# Terrariumsteuerung.net
KiCad netlist of a schematic drawn in EAGLE
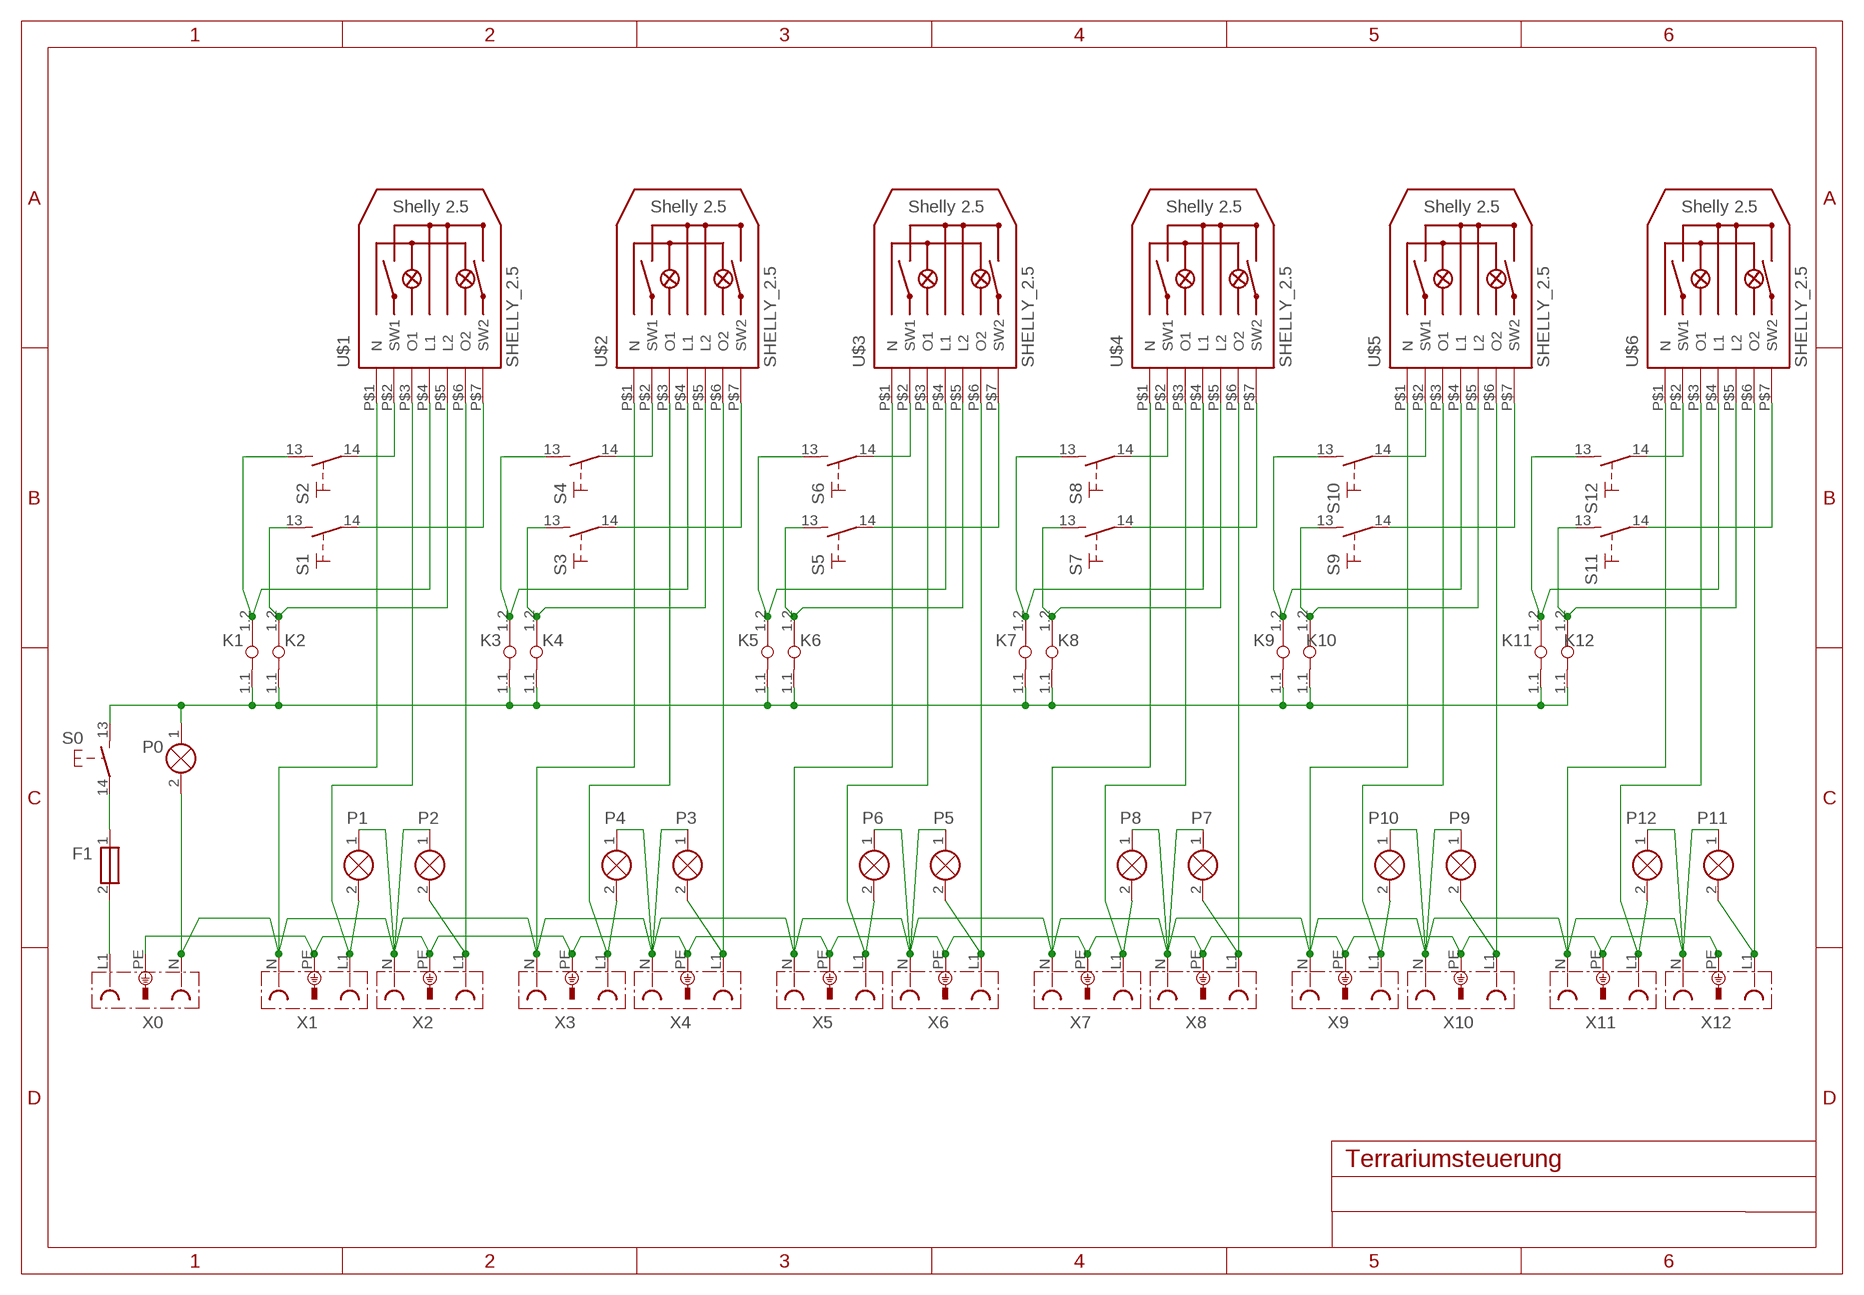
[diagram p0: schematic, sheet 1]

(export (version "E")
  (design (tool "Eeschema 10.0.6"))
  (components
    (comp (ref "F1")
      (value "SICHERUNG_1-POL")
      (footprint "eagle-import:SICHERUNG_1-POL")
      (libsource (lib "eagle-import") (part "SICHERUNG_1-POL"))
    )
    (comp (ref "K1")
      (value "KLEMME_1-1")
      (footprint "eagle-import:KLEMME_1-1")
      (libsource (lib "eagle-import") (part "KLEMME_1-1"))
    )
    (comp (ref "K2")
      (value "KLEMME_1-1")
      (footprint "eagle-import:KLEMME_1-1")
      (libsource (lib "eagle-import") (part "KLEMME_1-1"))
    )
    (comp (ref "K3")
      (value "KLEMME_1-1")
      (footprint "eagle-import:KLEMME_1-1")
      (libsource (lib "eagle-import") (part "KLEMME_1-1"))
    )
    (comp (ref "K4")
      (value "KLEMME_1-1")
      (footprint "eagle-import:KLEMME_1-1")
      (libsource (lib "eagle-import") (part "KLEMME_1-1"))
    )
    (comp (ref "K5")
      (value "KLEMME_1-1")
      (footprint "eagle-import:KLEMME_1-1")
      (libsource (lib "eagle-import") (part "KLEMME_1-1"))
    )
    (comp (ref "K6")
      (value "KLEMME_1-1")
      (footprint "eagle-import:KLEMME_1-1")
      (libsource (lib "eagle-import") (part "KLEMME_1-1"))
    )
    (comp (ref "K7")
      (value "KLEMME_1-1")
      (footprint "eagle-import:KLEMME_1-1")
      (libsource (lib "eagle-import") (part "KLEMME_1-1"))
    )
    (comp (ref "K8")
      (value "KLEMME_1-1")
      (footprint "eagle-import:KLEMME_1-1")
      (libsource (lib "eagle-import") (part "KLEMME_1-1"))
    )
    (comp (ref "K9")
      (value "KLEMME_1-1")
      (footprint "eagle-import:KLEMME_1-1")
      (libsource (lib "eagle-import") (part "KLEMME_1-1"))
    )
    (comp (ref "K10")
      (value "KLEMME_1-1")
      (footprint "eagle-import:KLEMME_1-1")
      (libsource (lib "eagle-import") (part "KLEMME_1-1"))
    )
    (comp (ref "K11")
      (value "KLEMME_1-1")
      (footprint "eagle-import:KLEMME_1-1")
      (libsource (lib "eagle-import") (part "KLEMME_1-1"))
    )
    (comp (ref "K12")
      (value "KLEMME_1-1")
      (footprint "eagle-import:KLEMME_1-1")
      (libsource (lib "eagle-import") (part "KLEMME_1-1"))
    )
    (comp (ref "P0")
      (value "SIGNALLAMPE")
      (footprint "eagle-import:LAMPE")
      (libsource (lib "eagle-import") (part "SIGNALLAMPE"))
    )
    (comp (ref "P1")
      (value "SIGNALLAMPE")
      (footprint "eagle-import:LAMPE")
      (libsource (lib "eagle-import") (part "SIGNALLAMPE"))
    )
    (comp (ref "P2")
      (value "SIGNALLAMPE")
      (footprint "eagle-import:LAMPE")
      (libsource (lib "eagle-import") (part "SIGNALLAMPE"))
    )
    (comp (ref "P3")
      (value "SIGNALLAMPE")
      (footprint "eagle-import:LAMPE")
      (libsource (lib "eagle-import") (part "SIGNALLAMPE"))
    )
    (comp (ref "P4")
      (value "SIGNALLAMPE")
      (footprint "eagle-import:LAMPE")
      (libsource (lib "eagle-import") (part "SIGNALLAMPE"))
    )
    (comp (ref "P5")
      (value "SIGNALLAMPE")
      (footprint "eagle-import:LAMPE")
      (libsource (lib "eagle-import") (part "SIGNALLAMPE"))
    )
    (comp (ref "P6")
      (value "SIGNALLAMPE")
      (footprint "eagle-import:LAMPE")
      (libsource (lib "eagle-import") (part "SIGNALLAMPE"))
    )
    (comp (ref "P7")
      (value "SIGNALLAMPE")
      (footprint "eagle-import:LAMPE")
      (libsource (lib "eagle-import") (part "SIGNALLAMPE"))
    )
    (comp (ref "P8")
      (value "SIGNALLAMPE")
      (footprint "eagle-import:LAMPE")
      (libsource (lib "eagle-import") (part "SIGNALLAMPE"))
    )
    (comp (ref "P9")
      (value "SIGNALLAMPE")
      (footprint "eagle-import:LAMPE")
      (libsource (lib "eagle-import") (part "SIGNALLAMPE"))
    )
    (comp (ref "P10")
      (value "SIGNALLAMPE")
      (footprint "eagle-import:LAMPE")
      (libsource (lib "eagle-import") (part "SIGNALLAMPE"))
    )
    (comp (ref "P11")
      (value "SIGNALLAMPE")
      (footprint "eagle-import:LAMPE")
      (libsource (lib "eagle-import") (part "SIGNALLAMPE"))
    )
    (comp (ref "P12")
      (value "SIGNALLAMPE")
      (footprint "eagle-import:LAMPE")
      (libsource (lib "eagle-import") (part "SIGNALLAMPE"))
    )
    (comp (ref "S0")
      (value "TASTER_SCHLIESSER")
      (footprint "eagle-import:EINTASTER")
      (libsource (lib "eagle-import") (part "TASTER_SCHLIESSER"))
    )
    (comp (ref "S1")
      (value "SCHLIESSER_KIPPSCHALTER")
      (footprint "eagle-import:SCHLIESSER_KIPPSCHALTER")
      (libsource (lib "eagle-import") (part "SCHLIESSER_KIPPSCHALTER"))
    )
    (comp (ref "S2")
      (value "SCHLIESSER_KIPPSCHALTER")
      (footprint "eagle-import:SCHLIESSER_KIPPSCHALTER")
      (libsource (lib "eagle-import") (part "SCHLIESSER_KIPPSCHALTER"))
    )
    (comp (ref "S3")
      (value "SCHLIESSER_KIPPSCHALTER")
      (footprint "eagle-import:SCHLIESSER_KIPPSCHALTER")
      (libsource (lib "eagle-import") (part "SCHLIESSER_KIPPSCHALTER"))
    )
    (comp (ref "S4")
      (value "SCHLIESSER_KIPPSCHALTER")
      (footprint "eagle-import:SCHLIESSER_KIPPSCHALTER")
      (libsource (lib "eagle-import") (part "SCHLIESSER_KIPPSCHALTER"))
    )
    (comp (ref "S5")
      (value "SCHLIESSER_KIPPSCHALTER")
      (footprint "eagle-import:SCHLIESSER_KIPPSCHALTER")
      (libsource (lib "eagle-import") (part "SCHLIESSER_KIPPSCHALTER"))
    )
    (comp (ref "S6")
      (value "SCHLIESSER_KIPPSCHALTER")
      (footprint "eagle-import:SCHLIESSER_KIPPSCHALTER")
      (libsource (lib "eagle-import") (part "SCHLIESSER_KIPPSCHALTER"))
    )
    (comp (ref "S7")
      (value "SCHLIESSER_KIPPSCHALTER")
      (footprint "eagle-import:SCHLIESSER_KIPPSCHALTER")
      (libsource (lib "eagle-import") (part "SCHLIESSER_KIPPSCHALTER"))
    )
    (comp (ref "S8")
      (value "SCHLIESSER_KIPPSCHALTER")
      (footprint "eagle-import:SCHLIESSER_KIPPSCHALTER")
      (libsource (lib "eagle-import") (part "SCHLIESSER_KIPPSCHALTER"))
    )
    (comp (ref "S9")
      (value "SCHLIESSER_KIPPSCHALTER")
      (footprint "eagle-import:SCHLIESSER_KIPPSCHALTER")
      (libsource (lib "eagle-import") (part "SCHLIESSER_KIPPSCHALTER"))
    )
    (comp (ref "S10")
      (value "SCHLIESSER_KIPPSCHALTER")
      (footprint "eagle-import:SCHLIESSER_KIPPSCHALTER")
      (libsource (lib "eagle-import") (part "SCHLIESSER_KIPPSCHALTER"))
    )
    (comp (ref "S11")
      (value "SCHLIESSER_KIPPSCHALTER")
      (footprint "eagle-import:SCHLIESSER_KIPPSCHALTER")
      (libsource (lib "eagle-import") (part "SCHLIESSER_KIPPSCHALTER"))
    )
    (comp (ref "S12")
      (value "SCHLIESSER_KIPPSCHALTER")
      (footprint "eagle-import:SCHLIESSER_KIPPSCHALTER")
      (libsource (lib "eagle-import") (part "SCHLIESSER_KIPPSCHALTER"))
    )
    (comp (ref "U$1")
      (value "SHELLY_2.5")
      (footprint "eagle-import:SHELLY_2.5")
      (libsource (lib "eagle-import") (part "SHELLY_2.5"))
    )
    (comp (ref "U$2")
      (value "SHELLY_2.5")
      (footprint "eagle-import:SHELLY_2.5")
      (libsource (lib "eagle-import") (part "SHELLY_2.5"))
    )
    (comp (ref "U$3")
      (value "SHELLY_2.5")
      (footprint "eagle-import:SHELLY_2.5")
      (libsource (lib "eagle-import") (part "SHELLY_2.5"))
    )
    (comp (ref "U$4")
      (value "SHELLY_2.5")
      (footprint "eagle-import:SHELLY_2.5")
      (libsource (lib "eagle-import") (part "SHELLY_2.5"))
    )
    (comp (ref "U$5")
      (value "SHELLY_2.5")
      (footprint "eagle-import:SHELLY_2.5")
      (libsource (lib "eagle-import") (part "SHELLY_2.5"))
    )
    (comp (ref "U$6")
      (value "SHELLY_2.5")
      (footprint "eagle-import:SHELLY_2.5")
      (libsource (lib "eagle-import") (part "SHELLY_2.5"))
    )
    (comp (ref "X0")
      (value "STECKDOSE")
      (footprint "eagle-import:STECKDOSE")
      (libsource (lib "eagle-import") (part "STECKDOSE"))
    )
    (comp (ref "X1")
      (value "STECKDOSE")
      (footprint "eagle-import:STECKDOSE")
      (libsource (lib "eagle-import") (part "STECKDOSE"))
    )
    (comp (ref "X2")
      (value "STECKDOSE")
      (footprint "eagle-import:STECKDOSE")
      (libsource (lib "eagle-import") (part "STECKDOSE"))
    )
    (comp (ref "X3")
      (value "STECKDOSE")
      (footprint "eagle-import:STECKDOSE")
      (libsource (lib "eagle-import") (part "STECKDOSE"))
    )
    (comp (ref "X4")
      (value "STECKDOSE")
      (footprint "eagle-import:STECKDOSE")
      (libsource (lib "eagle-import") (part "STECKDOSE"))
    )
    (comp (ref "X5")
      (value "STECKDOSE")
      (footprint "eagle-import:STECKDOSE")
      (libsource (lib "eagle-import") (part "STECKDOSE"))
    )
    (comp (ref "X6")
      (value "STECKDOSE")
      (footprint "eagle-import:STECKDOSE")
      (libsource (lib "eagle-import") (part "STECKDOSE"))
    )
    (comp (ref "X7")
      (value "STECKDOSE")
      (footprint "eagle-import:STECKDOSE")
      (libsource (lib "eagle-import") (part "STECKDOSE"))
    )
    (comp (ref "X8")
      (value "STECKDOSE")
      (footprint "eagle-import:STECKDOSE")
      (libsource (lib "eagle-import") (part "STECKDOSE"))
    )
    (comp (ref "X9")
      (value "STECKDOSE")
      (footprint "eagle-import:STECKDOSE")
      (libsource (lib "eagle-import") (part "STECKDOSE"))
    )
    (comp (ref "X10")
      (value "STECKDOSE")
      (footprint "eagle-import:STECKDOSE")
      (libsource (lib "eagle-import") (part "STECKDOSE"))
    )
    (comp (ref "X11")
      (value "STECKDOSE")
      (footprint "eagle-import:STECKDOSE")
      (libsource (lib "eagle-import") (part "STECKDOSE"))
    )
    (comp (ref "X12")
      (value "STECKDOSE")
      (footprint "eagle-import:STECKDOSE")
      (libsource (lib "eagle-import") (part "STECKDOSE"))
    )
  )
  (nets
    (net (code "1") (name "Net-(F1-Pad1)") (class "Default")
      (node (ref "F1") (pin "1") (pinfunction "1_1") (pintype "passive"))
      (node (ref "S0") (pin "14") (pinfunction "14_14") (pintype "passive"))
    )
    (net (code "2") (name "Net-(F1-Pad2)") (class "Default")
      (node (ref "F1") (pin "2") (pinfunction "2_2") (pintype "passive"))
      (node (ref "X0") (pin "L1") (pinfunction "L1_L1") (pintype "passive"))
    )
    (net (code "3") (name "Net-(P0-X1)") (class "Default")
      (node (ref "K1") (pin "1.1") (pinfunction "1.1_1.1") (pintype "passive"))
      (node (ref "K10") (pin "1.1") (pinfunction "1.1_1.1") (pintype "passive"))
      (node (ref "K11") (pin "1.1") (pinfunction "1.1_1.1") (pintype "passive"))
      (node (ref "K12") (pin "1.1") (pinfunction "1.1_1.1") (pintype "passive"))
      (node (ref "K2") (pin "1.1") (pinfunction "1.1_1.1") (pintype "passive"))
      (node (ref "K3") (pin "1.1") (pinfunction "1.1_1.1") (pintype "passive"))
      (node (ref "K4") (pin "1.1") (pinfunction "1.1_1.1") (pintype "passive"))
      (node (ref "K5") (pin "1.1") (pinfunction "1.1_1.1") (pintype "passive"))
      (node (ref "K6") (pin "1.1") (pinfunction "1.1_1.1") (pintype "passive"))
      (node (ref "K7") (pin "1.1") (pinfunction "1.1_1.1") (pintype "passive"))
      (node (ref "K8") (pin "1.1") (pinfunction "1.1_1.1") (pintype "passive"))
      (node (ref "K9") (pin "1.1") (pinfunction "1.1_1.1") (pintype "passive"))
      (node (ref "P0") (pin "1") (pinfunction "X1_1") (pintype "passive"))
      (node (ref "S0") (pin "13") (pinfunction "13_13") (pintype "passive"))
    )
    (net (code "4") (name "Net-(P0-X2)") (class "Default")
      (node (ref "P0") (pin "2") (pinfunction "X2_2") (pintype "passive"))
      (node (ref "P1") (pin "1") (pinfunction "X1_1") (pintype "passive"))
      (node (ref "P10") (pin "1") (pinfunction "X1_1") (pintype "passive"))
      (node (ref "P11") (pin "1") (pinfunction "X1_1") (pintype "passive"))
      (node (ref "P12") (pin "1") (pinfunction "X1_1") (pintype "passive"))
      (node (ref "P2") (pin "1") (pinfunction "X1_1") (pintype "passive"))
      (node (ref "P3") (pin "1") (pinfunction "X1_1") (pintype "passive"))
      (node (ref "P4") (pin "1") (pinfunction "X1_1") (pintype "passive"))
      (node (ref "P5") (pin "1") (pinfunction "X1_1") (pintype "passive"))
      (node (ref "P6") (pin "1") (pinfunction "X1_1") (pintype "passive"))
      (node (ref "P7") (pin "1") (pinfunction "X1_1") (pintype "passive"))
      (node (ref "P8") (pin "1") (pinfunction "X1_1") (pintype "passive"))
      (node (ref "P9") (pin "1") (pinfunction "X1_1") (pintype "passive"))
      (node (ref "U$1") (pin "P$1") (pinfunction "N_P$1") (pintype "bidirectional"))
      (node (ref "U$2") (pin "P$1") (pinfunction "N_P$1") (pintype "bidirectional"))
      (node (ref "U$3") (pin "P$1") (pinfunction "N_P$1") (pintype "bidirectional"))
      (node (ref "U$4") (pin "P$1") (pinfunction "N_P$1") (pintype "bidirectional"))
      (node (ref "U$5") (pin "P$1") (pinfunction "N_P$1") (pintype "bidirectional"))
      (node (ref "U$6") (pin "P$1") (pinfunction "N_P$1") (pintype "bidirectional"))
      (node (ref "X0") (pin "N") (pinfunction "N_N") (pintype "passive"))
      (node (ref "X1") (pin "N") (pinfunction "N_N") (pintype "passive"))
      (node (ref "X10") (pin "N") (pinfunction "N_N") (pintype "passive"))
      (node (ref "X11") (pin "N") (pinfunction "N_N") (pintype "passive"))
      (node (ref "X12") (pin "N") (pinfunction "N_N") (pintype "passive"))
      (node (ref "X2") (pin "N") (pinfunction "N_N") (pintype "passive"))
      (node (ref "X3") (pin "N") (pinfunction "N_N") (pintype "passive"))
      (node (ref "X4") (pin "N") (pinfunction "N_N") (pintype "passive"))
      (node (ref "X5") (pin "N") (pinfunction "N_N") (pintype "passive"))
      (node (ref "X6") (pin "N") (pinfunction "N_N") (pintype "passive"))
      (node (ref "X7") (pin "N") (pinfunction "N_N") (pintype "passive"))
      (node (ref "X8") (pin "N") (pinfunction "N_N") (pintype "passive"))
      (node (ref "X9") (pin "N") (pinfunction "N_N") (pintype "passive"))
    )
    (net (code "5") (name "Net-(P1-X2)") (class "Default")
      (node (ref "P1") (pin "2") (pinfunction "X2_2") (pintype "passive"))
      (node (ref "U$1") (pin "P$3") (pinfunction "O1_P$3") (pintype "bidirectional"))
      (node (ref "X1") (pin "L1") (pinfunction "L1_L1") (pintype "passive"))
    )
    (net (code "6") (name "Net-(P2-X2)") (class "Default")
      (node (ref "P2") (pin "2") (pinfunction "X2_2") (pintype "passive"))
      (node (ref "U$1") (pin "P$6") (pinfunction "O2_P$6") (pintype "bidirectional"))
      (node (ref "X2") (pin "L1") (pinfunction "L1_L1") (pintype "passive"))
    )
    (net (code "7") (name "Net-(P3-X2)") (class "Default")
      (node (ref "P3") (pin "2") (pinfunction "X2_2") (pintype "passive"))
      (node (ref "U$2") (pin "P$6") (pinfunction "O2_P$6") (pintype "bidirectional"))
      (node (ref "X4") (pin "L1") (pinfunction "L1_L1") (pintype "passive"))
    )
    (net (code "8") (name "Net-(P4-X2)") (class "Default")
      (node (ref "P4") (pin "2") (pinfunction "X2_2") (pintype "passive"))
      (node (ref "U$2") (pin "P$3") (pinfunction "O1_P$3") (pintype "bidirectional"))
      (node (ref "X3") (pin "L1") (pinfunction "L1_L1") (pintype "passive"))
    )
    (net (code "9") (name "Net-(P5-X2)") (class "Default")
      (node (ref "P5") (pin "2") (pinfunction "X2_2") (pintype "passive"))
      (node (ref "U$3") (pin "P$6") (pinfunction "O2_P$6") (pintype "bidirectional"))
      (node (ref "X6") (pin "L1") (pinfunction "L1_L1") (pintype "passive"))
    )
    (net (code "10") (name "Net-(P6-X2)") (class "Default")
      (node (ref "P6") (pin "2") (pinfunction "X2_2") (pintype "passive"))
      (node (ref "U$3") (pin "P$3") (pinfunction "O1_P$3") (pintype "bidirectional"))
      (node (ref "X5") (pin "L1") (pinfunction "L1_L1") (pintype "passive"))
    )
    (net (code "11") (name "Net-(P7-X2)") (class "Default")
      (node (ref "P7") (pin "2") (pinfunction "X2_2") (pintype "passive"))
      (node (ref "U$4") (pin "P$6") (pinfunction "O2_P$6") (pintype "bidirectional"))
      (node (ref "X8") (pin "L1") (pinfunction "L1_L1") (pintype "passive"))
    )
    (net (code "12") (name "Net-(P8-X2)") (class "Default")
      (node (ref "P8") (pin "2") (pinfunction "X2_2") (pintype "passive"))
      (node (ref "U$4") (pin "P$3") (pinfunction "O1_P$3") (pintype "bidirectional"))
      (node (ref "X7") (pin "L1") (pinfunction "L1_L1") (pintype "passive"))
    )
    (net (code "13") (name "Net-(P9-X2)") (class "Default")
      (node (ref "P9") (pin "2") (pinfunction "X2_2") (pintype "passive"))
      (node (ref "U$5") (pin "P$6") (pinfunction "O2_P$6") (pintype "bidirectional"))
      (node (ref "X10") (pin "L1") (pinfunction "L1_L1") (pintype "passive"))
    )
    (net (code "14") (name "Net-(P10-X2)") (class "Default")
      (node (ref "P10") (pin "2") (pinfunction "X2_2") (pintype "passive"))
      (node (ref "U$5") (pin "P$3") (pinfunction "O1_P$3") (pintype "bidirectional"))
      (node (ref "X9") (pin "L1") (pinfunction "L1_L1") (pintype "passive"))
    )
    (net (code "15") (name "Net-(P11-X2)") (class "Default")
      (node (ref "P11") (pin "2") (pinfunction "X2_2") (pintype "passive"))
      (node (ref "U$6") (pin "P$6") (pinfunction "O2_P$6") (pintype "bidirectional"))
      (node (ref "X12") (pin "L1") (pinfunction "L1_L1") (pintype "passive"))
    )
    (net (code "16") (name "Net-(P12-X2)") (class "Default")
      (node (ref "P12") (pin "2") (pinfunction "X2_2") (pintype "passive"))
      (node (ref "U$6") (pin "P$3") (pinfunction "O1_P$3") (pintype "bidirectional"))
      (node (ref "X11") (pin "L1") (pinfunction "L1_L1") (pintype "passive"))
    )
    (net (code "17") (name "Net-(S1-3)") (class "Default")
      (node (ref "K2") (pin "1.2") (pinfunction "1.2_1.2") (pintype "passive"))
      (node (ref "S1") (pin "13") (pinfunction "3_13") (pintype "input"))
      (node (ref "U$1") (pin "P$5") (pinfunction "L2_P$5") (pintype "bidirectional"))
    )
    (net (code "18") (name "Net-(S1-4)") (class "Default")
      (node (ref "S1") (pin "14") (pinfunction "4_14") (pintype "input"))
      (node (ref "U$1") (pin "P$7") (pinfunction "SW2_P$7") (pintype "bidirectional"))
    )
    (net (code "19") (name "Net-(S2-3)") (class "Default")
      (node (ref "K1") (pin "1.2") (pinfunction "1.2_1.2") (pintype "passive"))
      (node (ref "S2") (pin "13") (pinfunction "3_13") (pintype "input"))
      (node (ref "U$1") (pin "P$4") (pinfunction "L1_P$4") (pintype "bidirectional"))
    )
    (net (code "20") (name "Net-(S2-4)") (class "Default")
      (node (ref "S2") (pin "14") (pinfunction "4_14") (pintype "input"))
      (node (ref "U$1") (pin "P$2") (pinfunction "SW1_P$2") (pintype "bidirectional"))
    )
    (net (code "21") (name "Net-(S3-3)") (class "Default")
      (node (ref "K4") (pin "1.2") (pinfunction "1.2_1.2") (pintype "passive"))
      (node (ref "S3") (pin "13") (pinfunction "3_13") (pintype "input"))
      (node (ref "U$2") (pin "P$5") (pinfunction "L2_P$5") (pintype "bidirectional"))
    )
    (net (code "22") (name "Net-(S3-4)") (class "Default")
      (node (ref "S3") (pin "14") (pinfunction "4_14") (pintype "input"))
      (node (ref "U$2") (pin "P$7") (pinfunction "SW2_P$7") (pintype "bidirectional"))
    )
    (net (code "23") (name "Net-(S4-3)") (class "Default")
      (node (ref "K3") (pin "1.2") (pinfunction "1.2_1.2") (pintype "passive"))
      (node (ref "S4") (pin "13") (pinfunction "3_13") (pintype "input"))
      (node (ref "U$2") (pin "P$4") (pinfunction "L1_P$4") (pintype "bidirectional"))
    )
    (net (code "24") (name "Net-(S4-4)") (class "Default")
      (node (ref "S4") (pin "14") (pinfunction "4_14") (pintype "input"))
      (node (ref "U$2") (pin "P$2") (pinfunction "SW1_P$2") (pintype "bidirectional"))
    )
    (net (code "25") (name "Net-(S5-3)") (class "Default")
      (node (ref "K6") (pin "1.2") (pinfunction "1.2_1.2") (pintype "passive"))
      (node (ref "S5") (pin "13") (pinfunction "3_13") (pintype "input"))
      (node (ref "U$3") (pin "P$5") (pinfunction "L2_P$5") (pintype "bidirectional"))
    )
    (net (code "26") (name "Net-(S5-4)") (class "Default")
      (node (ref "S5") (pin "14") (pinfunction "4_14") (pintype "input"))
      (node (ref "U$3") (pin "P$7") (pinfunction "SW2_P$7") (pintype "bidirectional"))
    )
    (net (code "27") (name "Net-(S6-3)") (class "Default")
      (node (ref "K5") (pin "1.2") (pinfunction "1.2_1.2") (pintype "passive"))
      (node (ref "S6") (pin "13") (pinfunction "3_13") (pintype "input"))
      (node (ref "U$3") (pin "P$4") (pinfunction "L1_P$4") (pintype "bidirectional"))
    )
    (net (code "28") (name "Net-(S6-4)") (class "Default")
      (node (ref "S6") (pin "14") (pinfunction "4_14") (pintype "input"))
      (node (ref "U$3") (pin "P$2") (pinfunction "SW1_P$2") (pintype "bidirectional"))
    )
    (net (code "29") (name "Net-(S7-3)") (class "Default")
      (node (ref "K8") (pin "1.2") (pinfunction "1.2_1.2") (pintype "passive"))
      (node (ref "S7") (pin "13") (pinfunction "3_13") (pintype "input"))
      (node (ref "U$4") (pin "P$5") (pinfunction "L2_P$5") (pintype "bidirectional"))
    )
    (net (code "30") (name "Net-(S7-4)") (class "Default")
      (node (ref "S7") (pin "14") (pinfunction "4_14") (pintype "input"))
      (node (ref "U$4") (pin "P$7") (pinfunction "SW2_P$7") (pintype "bidirectional"))
    )
    (net (code "31") (name "Net-(S8-3)") (class "Default")
      (node (ref "K7") (pin "1.2") (pinfunction "1.2_1.2") (pintype "passive"))
      (node (ref "S8") (pin "13") (pinfunction "3_13") (pintype "input"))
      (node (ref "U$4") (pin "P$4") (pinfunction "L1_P$4") (pintype "bidirectional"))
    )
    (net (code "32") (name "Net-(S8-4)") (class "Default")
      (node (ref "S8") (pin "14") (pinfunction "4_14") (pintype "input"))
      (node (ref "U$4") (pin "P$2") (pinfunction "SW1_P$2") (pintype "bidirectional"))
    )
    (net (code "33") (name "Net-(S9-3)") (class "Default")
      (node (ref "K10") (pin "1.2") (pinfunction "1.2_1.2") (pintype "passive"))
      (node (ref "S9") (pin "13") (pinfunction "3_13") (pintype "input"))
      (node (ref "U$5") (pin "P$5") (pinfunction "L2_P$5") (pintype "bidirectional"))
    )
    (net (code "34") (name "Net-(S9-4)") (class "Default")
      (node (ref "S9") (pin "14") (pinfunction "4_14") (pintype "input"))
      (node (ref "U$5") (pin "P$7") (pinfunction "SW2_P$7") (pintype "bidirectional"))
    )
    (net (code "35") (name "Net-(S10-3)") (class "Default")
      (node (ref "K9") (pin "1.2") (pinfunction "1.2_1.2") (pintype "passive"))
      (node (ref "S10") (pin "13") (pinfunction "3_13") (pintype "input"))
      (node (ref "U$5") (pin "P$4") (pinfunction "L1_P$4") (pintype "bidirectional"))
    )
    (net (code "36") (name "Net-(S10-4)") (class "Default")
      (node (ref "S10") (pin "14") (pinfunction "4_14") (pintype "input"))
      (node (ref "U$5") (pin "P$2") (pinfunction "SW1_P$2") (pintype "bidirectional"))
    )
    (net (code "37") (name "Net-(S11-3)") (class "Default")
      (node (ref "K12") (pin "1.2") (pinfunction "1.2_1.2") (pintype "passive"))
      (node (ref "S11") (pin "13") (pinfunction "3_13") (pintype "input"))
      (node (ref "U$6") (pin "P$5") (pinfunction "L2_P$5") (pintype "bidirectional"))
    )
    (net (code "38") (name "Net-(S11-4)") (class "Default")
      (node (ref "S11") (pin "14") (pinfunction "4_14") (pintype "input"))
      (node (ref "U$6") (pin "P$7") (pinfunction "SW2_P$7") (pintype "bidirectional"))
    )
    (net (code "39") (name "Net-(S12-3)") (class "Default")
      (node (ref "K11") (pin "1.2") (pinfunction "1.2_1.2") (pintype "passive"))
      (node (ref "S12") (pin "13") (pinfunction "3_13") (pintype "input"))
      (node (ref "U$6") (pin "P$4") (pinfunction "L1_P$4") (pintype "bidirectional"))
    )
    (net (code "40") (name "Net-(S12-4)") (class "Default")
      (node (ref "S12") (pin "14") (pinfunction "4_14") (pintype "input"))
      (node (ref "U$6") (pin "P$2") (pinfunction "SW1_P$2") (pintype "bidirectional"))
    )
    (net (code "41") (name "Net-(X0-PadPE)") (class "Default")
      (node (ref "X0") (pin "PE") (pinfunction "PE_PE") (pintype "passive"))
      (node (ref "X1") (pin "PE") (pinfunction "PE_PE") (pintype "passive"))
      (node (ref "X10") (pin "PE") (pinfunction "PE_PE") (pintype "passive"))
      (node (ref "X11") (pin "PE") (pinfunction "PE_PE") (pintype "passive"))
      (node (ref "X12") (pin "PE") (pinfunction "PE_PE") (pintype "passive"))
      (node (ref "X2") (pin "PE") (pinfunction "PE_PE") (pintype "passive"))
      (node (ref "X3") (pin "PE") (pinfunction "PE_PE") (pintype "passive"))
      (node (ref "X4") (pin "PE") (pinfunction "PE_PE") (pintype "passive"))
      (node (ref "X5") (pin "PE") (pinfunction "PE_PE") (pintype "passive"))
      (node (ref "X6") (pin "PE") (pinfunction "PE_PE") (pintype "passive"))
      (node (ref "X7") (pin "PE") (pinfunction "PE_PE") (pintype "passive"))
      (node (ref "X8") (pin "PE") (pinfunction "PE_PE") (pintype "passive"))
      (node (ref "X9") (pin "PE") (pinfunction "PE_PE") (pintype "passive"))
    )
  )
)
